# small_encoder_board.net
KiCad netlist of a schematic drawn in EAGLE
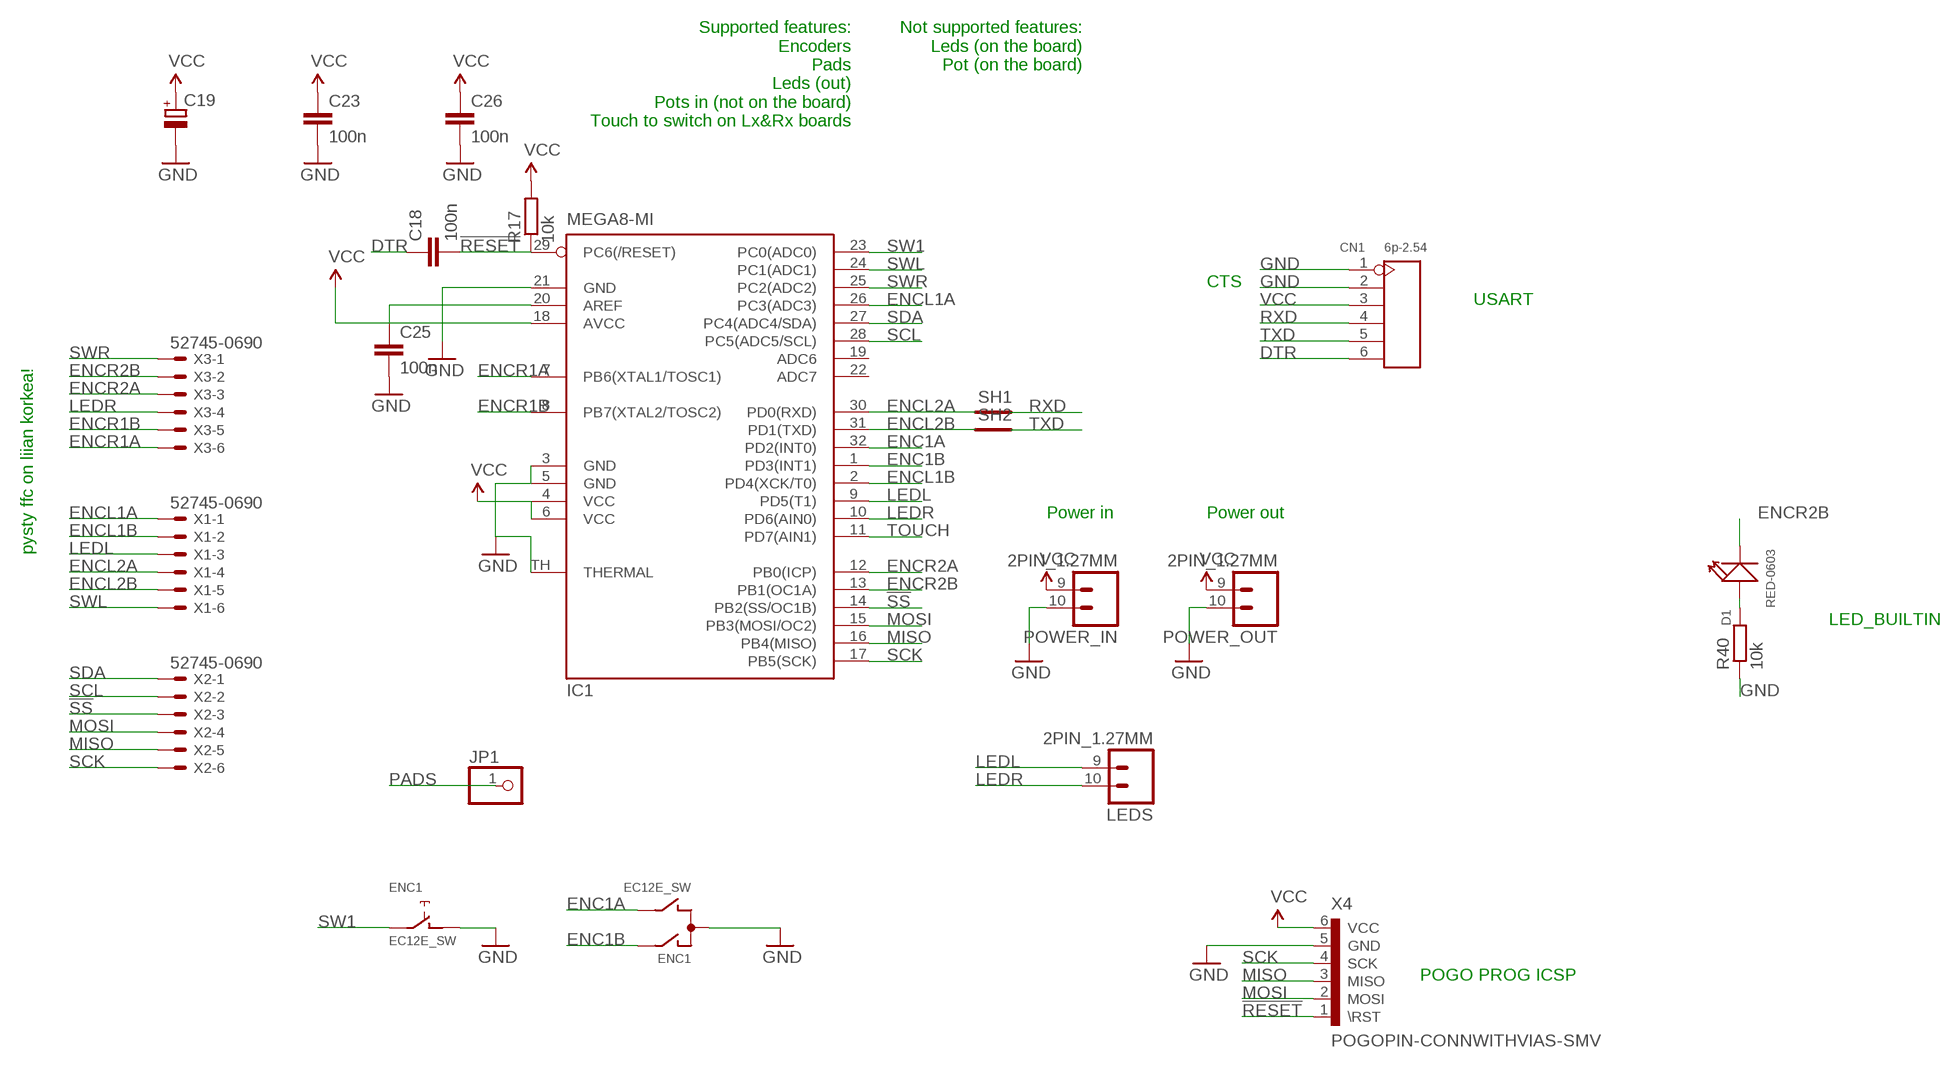
[diagram p0: schematic, sheet 1]
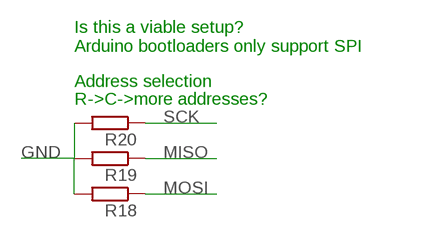
[diagram p1: schematic, sheet 2]
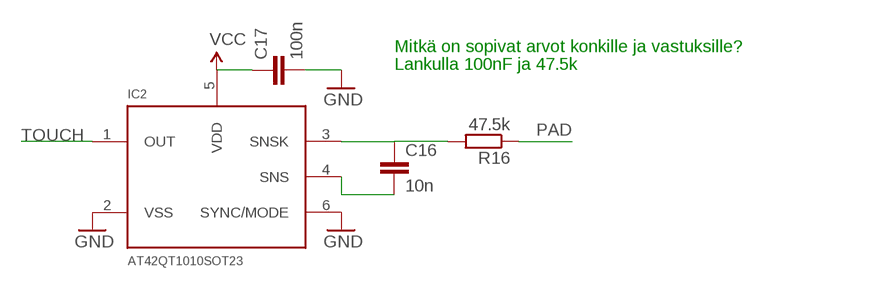
[diagram p2: schematic, sheet 3]
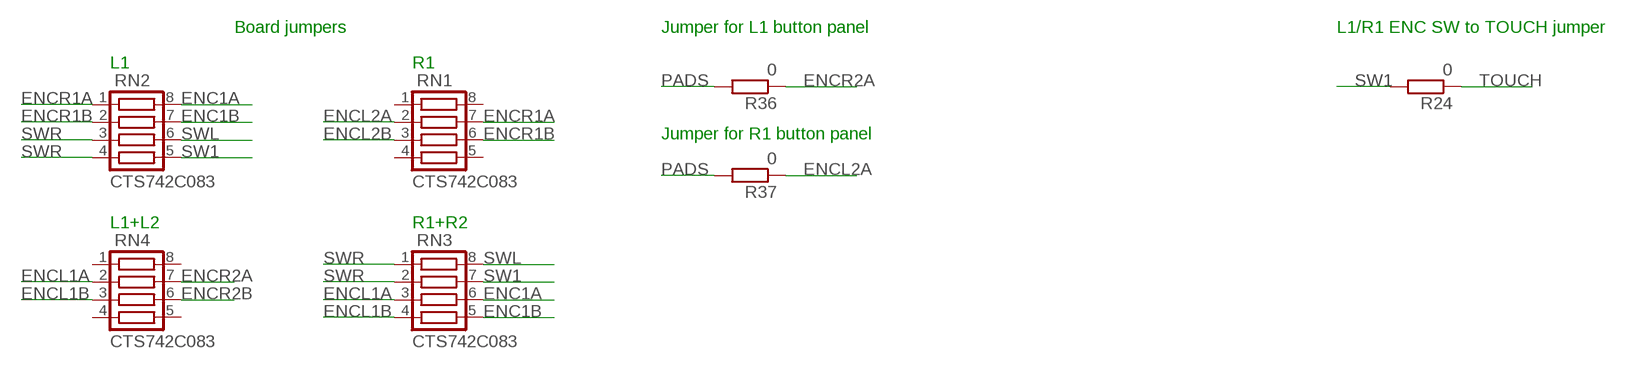
[diagram p3: schematic, sheet 4]

(export (version "E")
  (design (tool "Eeschema 10.0.6"))
  (components
    (comp (ref "C18")
      (value "100n")
      (footprint "eagle-import:0603-CAP")
      (libsource (lib "eagle-import") (part "CAP0603-CAP"))
    )
    (comp (ref "C19")
      (value "CPOL-EUC")
      (footprint "eagle-import:PANASONIC_C")
      (libsource (lib "eagle-import") (part "CPOL-EUC"))
    )
    (comp (ref "C23")
      (value "100n")
      (footprint "eagle-import:0603-CAP")
      (libsource (lib "eagle-import") (part "CAP0603-CAP"))
    )
    (comp (ref "C25")
      (value "100n")
      (footprint "eagle-import:0603-CAP")
      (libsource (lib "eagle-import") (part "CAP0603-CAP"))
    )
    (comp (ref "C26")
      (value "100n")
      (footprint "eagle-import:0603-CAP")
      (libsource (lib "eagle-import") (part "CAP0603-CAP"))
    )
    (comp (ref "CN1")
      (value "6p-2.54")
      (footprint "eagle-import:H6-2.54")
      (fields (field (name "MPN") "F185-1106A1BSYC1"))
      (libsource (lib "eagle-import") (part "DIP-BLACK-FEMALE-HEADER-VERT(6P-2.54)"))
    )
    (comp (ref "D1")
      (value "RED-0603")
      (footprint "eagle-import:LED-0603")
      (fields (field (name "MPN") "19-217-R6C-AL1M2VY-3T"))
      (libsource (lib "eagle-import") (part "LED-SMD-RED-DIFFUSED(0603)"))
    )
    (comp (ref "ENC1")
      (value "EC12E_SW")
      (footprint "eagle-import:ALPS_EC12E_SW")
      (fields (field (name "MPN") "EC12E2424407"))
      (libsource (lib "eagle-import") (part "EC12E_SW"))
    )
    (comp (ref "IC1")
      (value "MEGA8-MI")
      (footprint "eagle-import:MLF32-TH")
      (fields (field (name "MPN") "ATMEGA88PA-MU"))
      (libsource (lib "eagle-import") (part "MEGA8-MI"))
    )
    (comp (ref "JP1")
      (value "PINHD-1X1")
      (footprint "eagle-import:1X01")
      (libsource (lib "eagle-import") (part "PINHD-1X1"))
    )
    (comp (ref "LEDS")
      (value "2PIN_1.27MM")
      (footprint "eagle-import:1X02_1.27MM_NO_SILK")
      (libsource (lib "eagle-import") (part "2PIN_1.27MM"))
    )
    (comp (ref "POWER_IN")
      (value "2PIN_1.27MM")
      (footprint "eagle-import:1X02_1.27MM_NO_SILK")
      (libsource (lib "eagle-import") (part "2PIN_1.27MM"))
    )
    (comp (ref "POWER_OUT")
      (value "2PIN_1.27MM")
      (footprint "eagle-import:1X02_1.27MM_NO_SILK")
      (libsource (lib "eagle-import") (part "2PIN_1.27MM"))
    )
    (comp (ref "R17")
      (value "10k")
      (footprint "eagle-import:R0603")
      (libsource (lib "eagle-import") (part "R-EU_R0603"))
    )
    (comp (ref "R40")
      (value "10k")
      (footprint "eagle-import:R0603")
      (libsource (lib "eagle-import") (part "R-EU_R0603"))
    )
    (comp (ref "SH1")
      (value "SHORT")
      (footprint "eagle-import:SHORT_TOP_8MIL")
      (libsource (lib "eagle-import") (part "SHORT"))
    )
    (comp (ref "SH2")
      (value "SHORT")
      (footprint "eagle-import:SHORT_TOP_8MIL")
      (libsource (lib "eagle-import") (part "SHORT"))
    )
    (comp (ref "X1")
      (value "52745-0690")
      (footprint "eagle-import:52745-0690")
      (fields (field (name "MF") "MOLEX"))
      (libsource (lib "eagle-import") (part "52745-0690"))
    )
    (comp (ref "X2")
      (value "52745-0690")
      (footprint "eagle-import:52745-0690")
      (fields (field (name "MF") "MOLEX"))
      (libsource (lib "eagle-import") (part "52745-0690"))
    )
    (comp (ref "X3")
      (value "52745-0690")
      (footprint "eagle-import:52745-0690")
      (fields (field (name "MF") "MOLEX"))
      (libsource (lib "eagle-import") (part "52745-0690"))
    )
    (comp (ref "X4")
      (value "POGOPIN-CONNWITHVIAS-SMV")
      (footprint "eagle-import:POGOPROG-CONN-OH-SMALLERVIAS")
      (libsource (lib "eagle-import") (part "POGOPIN-CONNWITHVIAS-SMV"))
    )
    (comp (ref "C16")
      (value "10n")
      (footprint "eagle-import:0603-CAP")
      (libsource (lib "eagle-import") (part "CAP0603-CAP"))
    )
    (comp (ref "C17")
      (value "100n")
      (footprint "eagle-import:0603-CAP")
      (libsource (lib "eagle-import") (part "CAP0603-CAP"))
    )
    (comp (ref "IC2")
      (value "AT42QT1010SOT23")
      (footprint "eagle-import:SOT23-6")
      (libsource (lib "eagle-import") (part "AT42QT1010SOT23"))
    )
    (comp (ref "R16")
      (value "47.5k")
      (footprint "eagle-import:R0603")
      (libsource (lib "eagle-import") (part "R-EU_R0603"))
    )
    (comp (ref "R24")
      (value "0")
      (footprint "eagle-import:R0603")
      (fields (field (name "SPICEPREFIX") "R"))
      (libsource (lib "eagle-import") (part "R-EU_R0603"))
    )
    (comp (ref "R36")
      (value "0")
      (footprint "eagle-import:R0603")
      (fields (field (name "SPICEPREFIX") "R"))
      (libsource (lib "eagle-import") (part "R-EU_R0603"))
    )
    (comp (ref "R37")
      (value "0")
      (footprint "eagle-import:R0603")
      (fields (field (name "SPICEPREFIX") "R"))
      (libsource (lib "eagle-import") (part "R-EU_R0603"))
    )
    (comp (ref "RN1")
      (value "CTS742C083")
      (footprint "eagle-import:CTS742C083")
      (libsource (lib "eagle-import") (part "CTS742C083"))
    )
    (comp (ref "RN2")
      (value "CTS742C083")
      (footprint "eagle-import:CTS742C083")
      (libsource (lib "eagle-import") (part "CTS742C083"))
    )
    (comp (ref "RN3")
      (value "CTS742C083")
      (footprint "eagle-import:CTS742C083")
      (libsource (lib "eagle-import") (part "CTS742C083"))
    )
    (comp (ref "RN4")
      (value "CTS742C083")
      (footprint "eagle-import:CTS742C083")
      (libsource (lib "eagle-import") (part "CTS742C083"))
    )
    (comp (ref "R18")
      (value "R-EU_R0603")
      (footprint "eagle-import:R0603")
      (libsource (lib "eagle-import") (part "R-EU_R0603"))
    )
    (comp (ref "R19")
      (value "R-EU_R0603")
      (footprint "eagle-import:R0603")
      (libsource (lib "eagle-import") (part "R-EU_R0603"))
    )
    (comp (ref "R20")
      (value "R-EU_R0603")
      (footprint "eagle-import:R0603")
      (libsource (lib "eagle-import") (part "R-EU_R0603"))
    )
  )
  (nets
    (net (code "1") (name "DTR") (class "Default")
      (node (ref "C18") (pin "1") (pinfunction "1_1") (pintype "passive"))
      (node (ref "CN1") (pin "6") (pinfunction "6_6") (pintype "bidirectional"))
    )
    (net (code "2") (name "ENC1A") (class "Default")
      (node (ref "ENC1") (pin "B") (pinfunction "B_B") (pintype "passive"))
      (node (ref "IC1") (pin "32") (pinfunction "PD2(INT0)_32") (pintype "bidirectional"))
      (node (ref "RN2") (pin "8") (pinfunction "8_8") (pintype "passive"))
      (node (ref "RN3") (pin "6") (pinfunction "6_6") (pintype "passive"))
    )
    (net (code "3") (name "ENC1B") (class "Default")
      (node (ref "ENC1") (pin "A") (pinfunction "A_A") (pintype "passive"))
      (node (ref "IC1") (pin "1") (pinfunction "PD3(INT1)_1") (pintype "bidirectional"))
      (node (ref "RN2") (pin "7") (pinfunction "7_7") (pintype "passive"))
      (node (ref "RN3") (pin "5") (pinfunction "5_5") (pintype "passive"))
    )
    (net (code "4") (name "ENCL1A") (class "Default")
      (node (ref "IC1") (pin "26") (pinfunction "PC3(ADC3)_26") (pintype "bidirectional"))
      (node (ref "RN3") (pin "3") (pinfunction "3_3") (pintype "passive"))
      (node (ref "RN4") (pin "2") (pinfunction "2_2") (pintype "passive"))
      (node (ref "X1") (pin "1") (pinfunction "S_1") (pintype "passive"))
    )
    (net (code "5") (name "ENCL1B") (class "Default")
      (node (ref "IC1") (pin "2") (pinfunction "PD4(XCK/T0)_2") (pintype "bidirectional"))
      (node (ref "RN3") (pin "4") (pinfunction "4_4") (pintype "passive"))
      (node (ref "RN4") (pin "3") (pinfunction "3_3") (pintype "passive"))
      (node (ref "X1") (pin "2") (pinfunction "S_2") (pintype "passive"))
    )
    (net (code "6") (name "ENCL2A") (class "Default")
      (node (ref "IC1") (pin "30") (pinfunction "PD0(RXD)_30") (pintype "bidirectional"))
      (node (ref "R37") (pin "1") (pinfunction "1_1") (pintype "passive"))
      (node (ref "RN1") (pin "2") (pinfunction "2_2") (pintype "passive"))
      (node (ref "SH1") (pin "P$1") (pinfunction "P$1_P$1") (pintype "bidirectional"))
      (node (ref "X1") (pin "4") (pinfunction "S_4") (pintype "passive"))
    )
    (net (code "7") (name "ENCL2B") (class "Default")
      (node (ref "IC1") (pin "31") (pinfunction "PD1(TXD)_31") (pintype "bidirectional"))
      (node (ref "RN1") (pin "3") (pinfunction "3_3") (pintype "passive"))
      (node (ref "SH2") (pin "P$1") (pinfunction "P$1_P$1") (pintype "bidirectional"))
      (node (ref "X1") (pin "5") (pinfunction "S_5") (pintype "passive"))
    )
    (net (code "8") (name "ENCR1A") (class "Default")
      (node (ref "IC1") (pin "7") (pinfunction "PB6(XTAL1/TOSC1)_7") (pintype "bidirectional"))
      (node (ref "RN1") (pin "7") (pinfunction "7_7") (pintype "passive"))
      (node (ref "RN2") (pin "1") (pinfunction "1_1") (pintype "passive"))
      (node (ref "X3") (pin "6") (pinfunction "S_6") (pintype "passive"))
    )
    (net (code "9") (name "ENCR1B") (class "Default")
      (node (ref "IC1") (pin "8") (pinfunction "PB7(XTAL2/TOSC2)_8") (pintype "bidirectional"))
      (node (ref "RN1") (pin "6") (pinfunction "6_6") (pintype "passive"))
      (node (ref "RN2") (pin "2") (pinfunction "2_2") (pintype "passive"))
      (node (ref "X3") (pin "5") (pinfunction "S_5") (pintype "passive"))
    )
    (net (code "10") (name "ENCR2A") (class "Default")
      (node (ref "IC1") (pin "12") (pinfunction "PB0(ICP)_12") (pintype "bidirectional"))
      (node (ref "R36") (pin "1") (pinfunction "1_1") (pintype "passive"))
      (node (ref "RN4") (pin "7") (pinfunction "7_7") (pintype "passive"))
      (node (ref "X3") (pin "3") (pinfunction "S_3") (pintype "passive"))
    )
    (net (code "11") (name "ENCR2B") (class "Default")
      (node (ref "D1") (pin "-") (pinfunction "-_-") (pintype "passive"))
      (node (ref "IC1") (pin "13") (pinfunction "PB1(OC1A)_13") (pintype "bidirectional"))
      (node (ref "RN4") (pin "6") (pinfunction "6_6") (pintype "passive"))
      (node (ref "X3") (pin "2") (pinfunction "S_2") (pintype "passive"))
    )
    (net (code "12") (name "GND") (class "Default")
      (node (ref "C17") (pin "2") (pinfunction "2_2") (pintype "passive"))
      (node (ref "C19") (pin "-") (pinfunction "-_-") (pintype "passive"))
      (node (ref "C23") (pin "2") (pinfunction "2_2") (pintype "passive"))
      (node (ref "C25") (pin "2") (pinfunction "2_2") (pintype "passive"))
      (node (ref "C26") (pin "2") (pinfunction "2_2") (pintype "passive"))
      (node (ref "CN1") (pin "1") (pinfunction "1_1") (pintype "bidirectional"))
      (node (ref "CN1") (pin "2") (pinfunction "2_2") (pintype "bidirectional"))
      (node (ref "ENC1") (pin "C") (pinfunction "C_C") (pintype "passive"))
      (node (ref "ENC1") (pin "D") (pinfunction "1_D") (pintype "passive"))
      (node (ref "IC1") (pin "21") (pinfunction "GND_21") (pintype "power_in"))
      (node (ref "IC1") (pin "3") (pinfunction "GND_3") (pintype "power_in"))
      (node (ref "IC1") (pin "5") (pinfunction "GND_5") (pintype "power_in"))
      (node (ref "IC1") (pin "TH") (pinfunction "THERMAL_TH") (pintype "passive"))
      (node (ref "IC2") (pin "2") (pinfunction "VSS_2") (pintype "bidirectional"))
      (node (ref "IC2") (pin "6") (pinfunction "SYNC/MODE_6") (pintype "bidirectional"))
      (node (ref "POWER_IN") (pin "10") (pinfunction "2_10") (pintype "passive"))
      (node (ref "POWER_OUT") (pin "10") (pinfunction "2_10") (pintype "passive"))
      (node (ref "R18") (pin "2") (pinfunction "2_2") (pintype "passive"))
      (node (ref "R19") (pin "2") (pinfunction "2_2") (pintype "passive"))
      (node (ref "R20") (pin "2") (pinfunction "2_2") (pintype "passive"))
      (node (ref "R40") (pin "1") (pinfunction "1_1") (pintype "passive"))
      (node (ref "X4") (pin "5") (pinfunction "GND_5") (pintype "bidirectional"))
    )
    (net (code "13") (name "LEDL") (class "Default")
      (node (ref "IC1") (pin "9") (pinfunction "PD5(T1)_9") (pintype "bidirectional"))
      (node (ref "LEDS") (pin "9") (pinfunction "1_9") (pintype "passive"))
      (node (ref "X1") (pin "3") (pinfunction "S_3") (pintype "passive"))
    )
    (net (code "14") (name "LEDR") (class "Default")
      (node (ref "IC1") (pin "10") (pinfunction "PD6(AIN0)_10") (pintype "bidirectional"))
      (node (ref "LEDS") (pin "10") (pinfunction "2_10") (pintype "passive"))
      (node (ref "X3") (pin "4") (pinfunction "S_4") (pintype "passive"))
    )
    (net (code "15") (name "MISO") (class "Default")
      (node (ref "IC1") (pin "16") (pinfunction "PB4(MISO)_16") (pintype "bidirectional"))
      (node (ref "R19") (pin "1") (pinfunction "1_1") (pintype "passive"))
      (node (ref "X2") (pin "5") (pinfunction "S_5") (pintype "passive"))
      (node (ref "X4") (pin "3") (pinfunction "MISO_3") (pintype "bidirectional"))
    )
    (net (code "16") (name "MOSI") (class "Default")
      (node (ref "IC1") (pin "15") (pinfunction "PB3(MOSI/OC2)_15") (pintype "bidirectional"))
      (node (ref "R18") (pin "1") (pinfunction "1_1") (pintype "passive"))
      (node (ref "X2") (pin "4") (pinfunction "S_4") (pintype "passive"))
      (node (ref "X4") (pin "2") (pinfunction "MOSI_2") (pintype "bidirectional"))
    )
    (net (code "17") (name "Net-(D1-Pad+)") (class "Default")
      (node (ref "D1") (pin "+") (pinfunction "+_+") (pintype "passive"))
      (node (ref "R40") (pin "2") (pinfunction "2_2") (pintype "passive"))
    )
    (net (code "18") (name "Net-(IC1-AREF)") (class "Default")
      (node (ref "C25") (pin "1") (pinfunction "1_1") (pintype "passive"))
      (node (ref "IC1") (pin "20") (pinfunction "AREF_20") (pintype "passive"))
    )
    (net (code "19") (name "Net-(IC2-SNS)") (class "Default")
      (node (ref "C16") (pin "2") (pinfunction "2_2") (pintype "passive"))
      (node (ref "IC2") (pin "4") (pinfunction "SNS_4") (pintype "bidirectional"))
    )
    (net (code "20") (name "Net-(IC2-SNSK)") (class "Default")
      (node (ref "C16") (pin "1") (pinfunction "1_1") (pintype "passive"))
      (node (ref "IC2") (pin "3") (pinfunction "SNSK_3") (pintype "bidirectional"))
      (node (ref "R16") (pin "2") (pinfunction "2_2") (pintype "passive"))
    )
    (net (code "21") (name "PAD") (class "Default")
      (node (ref "R16") (pin "1") (pinfunction "1_1") (pintype "passive"))
    )
    (net (code "22") (name "PADS") (class "Default")
      (node (ref "JP1") (pin "1") (pinfunction "1_1") (pintype "passive"))
      (node (ref "R36") (pin "2") (pinfunction "2_2") (pintype "passive"))
      (node (ref "R37") (pin "2") (pinfunction "2_2") (pintype "passive"))
    )
    (net (code "23") (name "RXD") (class "Default")
      (node (ref "CN1") (pin "4") (pinfunction "4_4") (pintype "bidirectional"))
      (node (ref "SH1") (pin "P$2") (pinfunction "P$2_P$2") (pintype "bidirectional"))
    )
    (net (code "24") (name "SCK") (class "Default")
      (node (ref "IC1") (pin "17") (pinfunction "PB5(SCK)_17") (pintype "bidirectional"))
      (node (ref "R20") (pin "1") (pinfunction "1_1") (pintype "passive"))
      (node (ref "X2") (pin "6") (pinfunction "S_6") (pintype "passive"))
      (node (ref "X4") (pin "4") (pinfunction "SCK_4") (pintype "bidirectional"))
    )
    (net (code "25") (name "SCL") (class "Default")
      (node (ref "IC1") (pin "28") (pinfunction "PC5(ADC5/SCL)_28") (pintype "bidirectional"))
      (node (ref "X2") (pin "2") (pinfunction "S_2") (pintype "passive"))
    )
    (net (code "26") (name "SDA") (class "Default")
      (node (ref "IC1") (pin "27") (pinfunction "PC4(ADC4/SDA)_27") (pintype "bidirectional"))
      (node (ref "X2") (pin "1") (pinfunction "S_1") (pintype "passive"))
    )
    (net (code "27") (name "SW1") (class "Default")
      (node (ref "ENC1") (pin "E") (pinfunction "2_E") (pintype "passive"))
      (node (ref "IC1") (pin "23") (pinfunction "PC0(ADC0)_23") (pintype "bidirectional"))
      (node (ref "R24") (pin "2") (pinfunction "2_2") (pintype "passive"))
      (node (ref "RN2") (pin "5") (pinfunction "5_5") (pintype "passive"))
      (node (ref "RN3") (pin "7") (pinfunction "7_7") (pintype "passive"))
    )
    (net (code "28") (name "SWL") (class "Default")
      (node (ref "IC1") (pin "24") (pinfunction "PC1(ADC1)_24") (pintype "bidirectional"))
      (node (ref "RN2") (pin "6") (pinfunction "6_6") (pintype "passive"))
      (node (ref "RN3") (pin "8") (pinfunction "8_8") (pintype "passive"))
      (node (ref "X1") (pin "6") (pinfunction "S_6") (pintype "passive"))
    )
    (net (code "29") (name "SWR") (class "Default")
      (node (ref "IC1") (pin "25") (pinfunction "PC2(ADC2)_25") (pintype "bidirectional"))
      (node (ref "RN2") (pin "3") (pinfunction "3_3") (pintype "passive"))
      (node (ref "RN2") (pin "4") (pinfunction "4_4") (pintype "passive"))
      (node (ref "RN3") (pin "1") (pinfunction "1_1") (pintype "passive"))
      (node (ref "RN3") (pin "2") (pinfunction "2_2") (pintype "passive"))
      (node (ref "X3") (pin "1") (pinfunction "S_1") (pintype "passive"))
    )
    (net (code "30") (name "TOUCH") (class "Default")
      (node (ref "IC1") (pin "11") (pinfunction "PD7(AIN1)_11") (pintype "bidirectional"))
      (node (ref "IC2") (pin "1") (pinfunction "OUT_1") (pintype "bidirectional"))
      (node (ref "R24") (pin "1") (pinfunction "1_1") (pintype "passive"))
    )
    (net (code "31") (name "TXD") (class "Default")
      (node (ref "CN1") (pin "5") (pinfunction "5_5") (pintype "bidirectional"))
      (node (ref "SH2") (pin "P$2") (pinfunction "P$2_P$2") (pintype "bidirectional"))
    )
    (net (code "32") (name "VCC") (class "Default")
      (node (ref "C17") (pin "1") (pinfunction "1_1") (pintype "passive"))
      (node (ref "C19") (pin "+") (pinfunction "+_+") (pintype "passive"))
      (node (ref "C23") (pin "1") (pinfunction "1_1") (pintype "passive"))
      (node (ref "C26") (pin "1") (pinfunction "1_1") (pintype "passive"))
      (node (ref "CN1") (pin "3") (pinfunction "3_3") (pintype "bidirectional"))
      (node (ref "IC1") (pin "18") (pinfunction "AVCC_18") (pintype "power_in"))
      (node (ref "IC1") (pin "4") (pinfunction "VCC_4") (pintype "power_in"))
      (node (ref "IC1") (pin "6") (pinfunction "VCC_6") (pintype "power_in"))
      (node (ref "IC2") (pin "5") (pinfunction "VDD_5") (pintype "bidirectional"))
      (node (ref "POWER_IN") (pin "9") (pinfunction "1_9") (pintype "passive"))
      (node (ref "POWER_OUT") (pin "9") (pinfunction "1_9") (pintype "passive"))
      (node (ref "R17") (pin "2") (pinfunction "2_2") (pintype "passive"))
      (node (ref "X4") (pin "6") (pinfunction "VCC_6") (pintype "bidirectional"))
    )
    (net (code "33") (name "unconnected-(IC1-ADC6-Pad19)") (class "Default")
      (node (ref "IC1") (pin "19") (pinfunction "ADC6_19") (pintype "bidirectional"))
    )
    (net (code "34") (name "unconnected-(IC1-ADC7-Pad22)") (class "Default")
      (node (ref "IC1") (pin "22") (pinfunction "ADC7_22") (pintype "bidirectional"))
    )
    (net (code "35") (name "unconnected-(RN1-Pad1)") (class "Default")
      (node (ref "RN1") (pin "1") (pinfunction "1_1") (pintype "passive"))
    )
    (net (code "36") (name "unconnected-(RN1-Pad4)") (class "Default")
      (node (ref "RN1") (pin "4") (pinfunction "4_4") (pintype "passive"))
    )
    (net (code "37") (name "unconnected-(RN1-Pad5)") (class "Default")
      (node (ref "RN1") (pin "5") (pinfunction "5_5") (pintype "passive"))
    )
    (net (code "38") (name "unconnected-(RN1-Pad8)") (class "Default")
      (node (ref "RN1") (pin "8") (pinfunction "8_8") (pintype "passive"))
    )
    (net (code "39") (name "unconnected-(RN4-Pad1)") (class "Default")
      (node (ref "RN4") (pin "1") (pinfunction "1_1") (pintype "passive"))
    )
    (net (code "40") (name "unconnected-(RN4-Pad4)") (class "Default")
      (node (ref "RN4") (pin "4") (pinfunction "4_4") (pintype "passive"))
    )
    (net (code "41") (name "unconnected-(RN4-Pad5)") (class "Default")
      (node (ref "RN4") (pin "5") (pinfunction "5_5") (pintype "passive"))
    )
    (net (code "42") (name "unconnected-(RN4-Pad8)") (class "Default")
      (node (ref "RN4") (pin "8") (pinfunction "8_8") (pintype "passive"))
    )
    (net (code "43") (name "~{RESET}") (class "Default")
      (node (ref "C18") (pin "2") (pinfunction "2_2") (pintype "passive"))
      (node (ref "IC1") (pin "29") (pinfunction "PC6(/RESET)_29") (pintype "bidirectional"))
      (node (ref "R17") (pin "1") (pinfunction "1_1") (pintype "passive"))
      (node (ref "X4") (pin "1") (pinfunction "\\RST_1") (pintype "bidirectional"))
    )
    (net (code "44") (name "~{SS}") (class "Default")
      (node (ref "IC1") (pin "14") (pinfunction "PB2(SS/OC1B)_14") (pintype "bidirectional"))
      (node (ref "X2") (pin "3") (pinfunction "S_3") (pintype "passive"))
    )
  )
)
